# ArduFrauenfelderCNC_0_1-b6.net
KiCad netlist of a schematic drawn in EAGLE
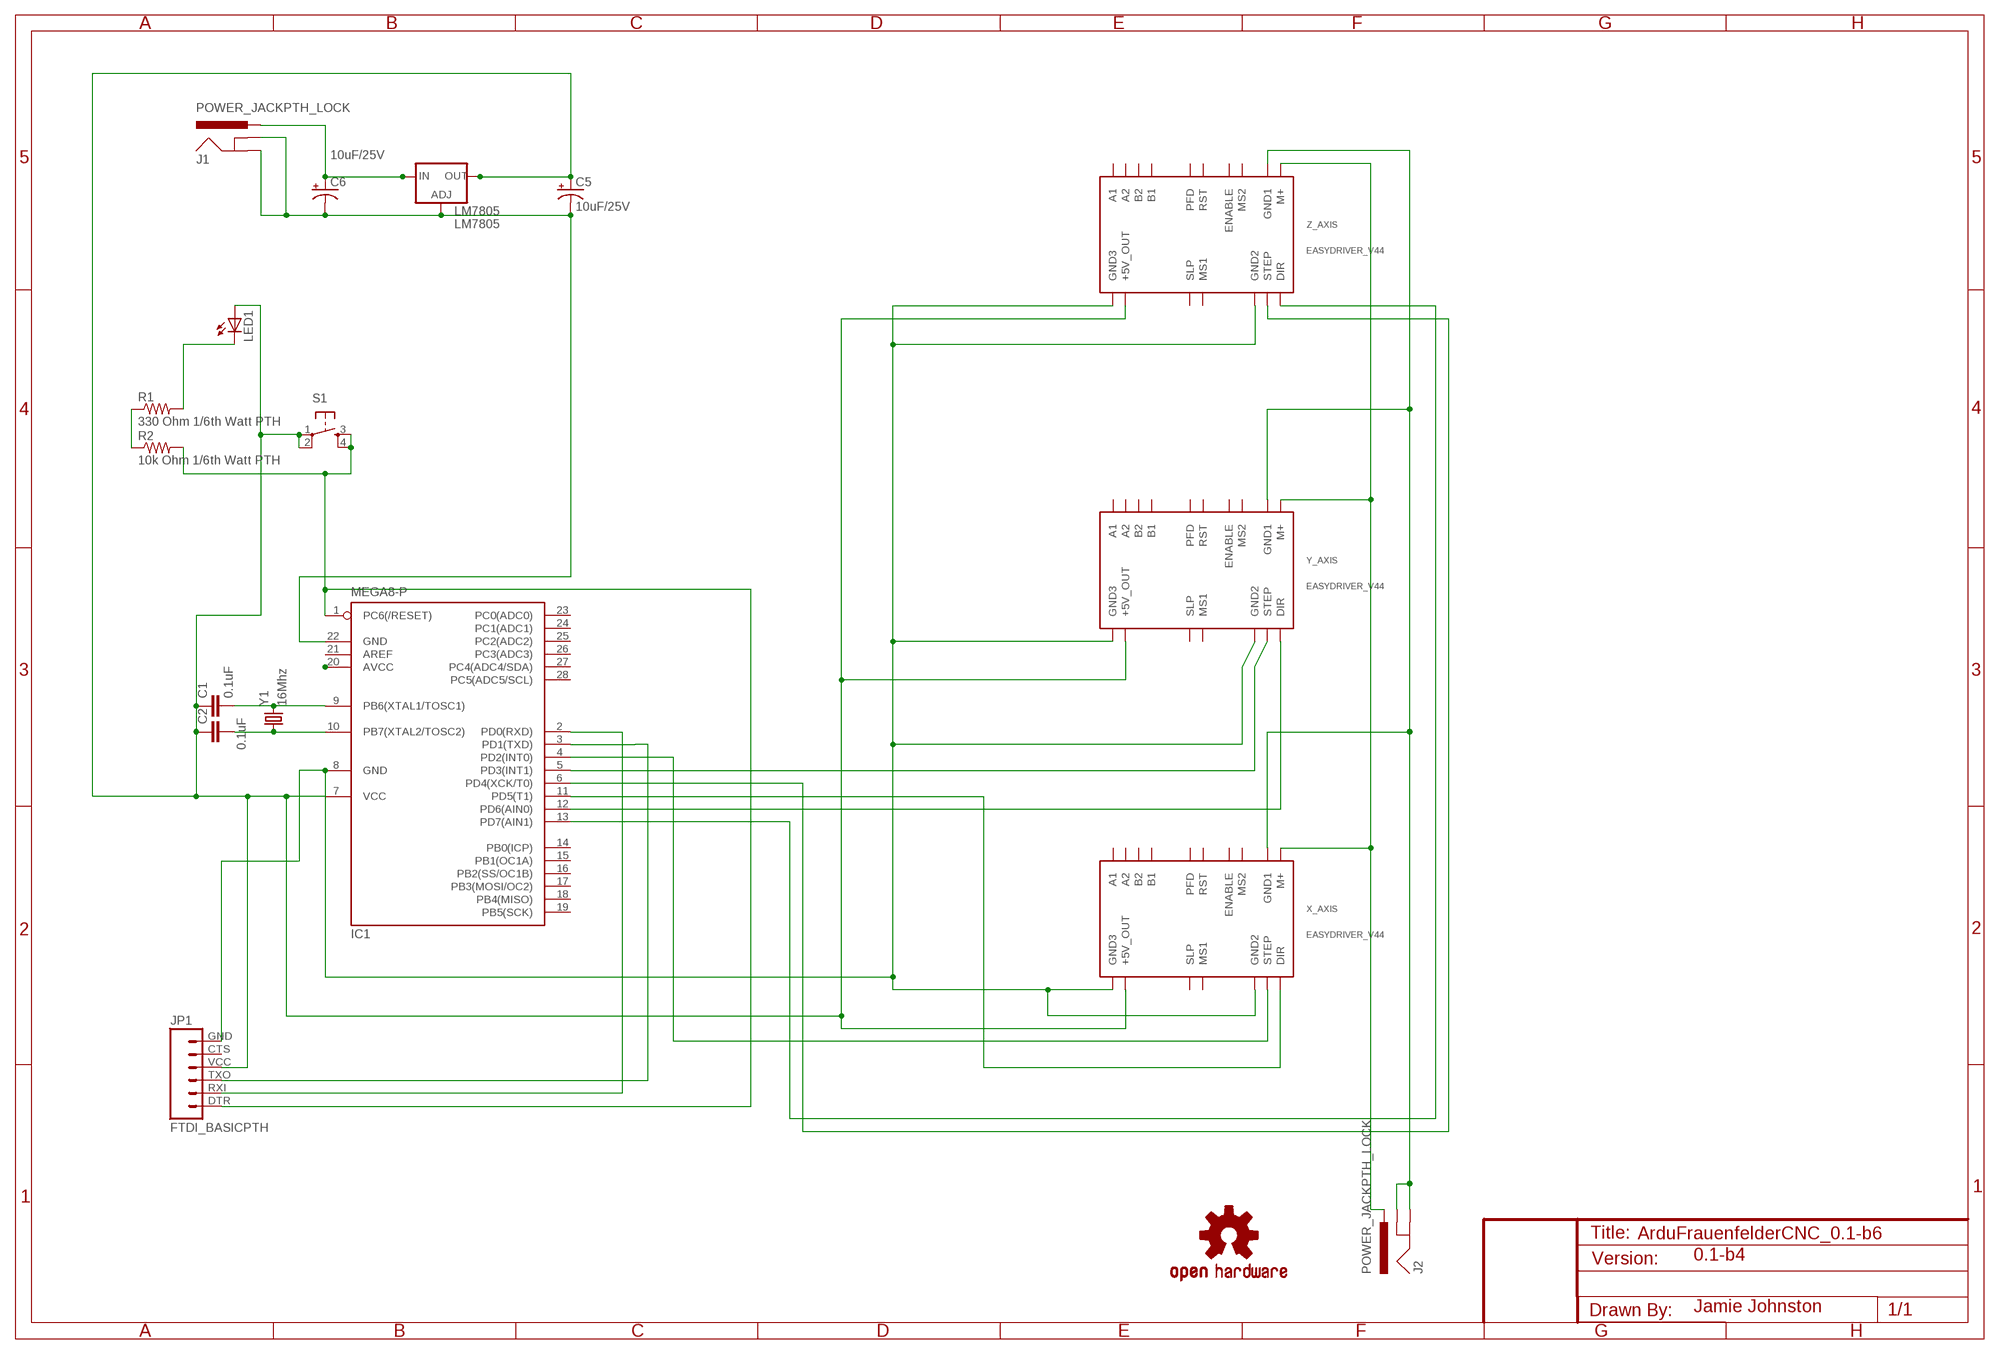
[diagram p0: schematic, sheet 1]

(export (version "E")
  (design (tool "Eeschema 10.0.6"))
  (components
    (comp (ref "C1")
      (value "0.1uF")
      (footprint "eagle-import:CAP-PTH-SMALL")
      (libsource (lib "eagle-import") (part "CAPPTH"))
    )
    (comp (ref "C2")
      (value "0.1uF")
      (footprint "eagle-import:CAP-PTH-SMALL")
      (libsource (lib "eagle-import") (part "CAPPTH"))
    )
    (comp (ref "C5")
      (value "10uF/25V")
      (footprint "eagle-import:CPOL-RADIAL-10UF-25V")
      (libsource (lib "eagle-import") (part "CAP_POLPTH2"))
    )
    (comp (ref "C6")
      (value "10uF/25V")
      (footprint "eagle-import:CPOL-RADIAL-10UF-25V")
      (libsource (lib "eagle-import") (part "CAP_POLPTH2"))
    )
    (comp (ref "IC1")
      (value "MEGA8-P")
      (footprint "eagle-import:DIL28-3")
      (libsource (lib "eagle-import") (part "MEGA8-P"))
    )
    (comp (ref "J1")
      (value "POWER_JACKPTH_LOCK")
      (footprint "eagle-import:POWER_JACK_PTH_LOCK")
      (libsource (lib "eagle-import") (part "POWER_JACKPTH_LOCK"))
    )
    (comp (ref "J2")
      (value "POWER_JACKPTH_LOCK")
      (footprint "eagle-import:POWER_JACK_PTH_LOCK")
      (libsource (lib "eagle-import") (part "POWER_JACKPTH_LOCK"))
    )
    (comp (ref "JP1")
      (value "FTDI_BASICPTH")
      (footprint "eagle-import:FTDI_BASIC")
      (libsource (lib "eagle-import") (part "FTDI_BASICPTH"))
    )
    (comp (ref "LED1")
      (value "LED5MM")
      (footprint "eagle-import:LED5MM")
      (libsource (lib "eagle-import") (part "LED5MM"))
    )
    (comp (ref "LM7805")
      (value "LM7805")
      (footprint "eagle-import:TO220-ADJ")
      (libsource (lib "eagle-import") (part "V_REG_317SINK"))
    )
    (comp (ref "R1")
      (value "330 Ohm 1/6th Watt PTH")
      (footprint "eagle-import:AXIAL-0.4")
      (libsource (lib "eagle-import") (part "RESISTORPTH-1/4W"))
    )
    (comp (ref "R2")
      (value "10k Ohm 1/6th Watt PTH")
      (footprint "eagle-import:AXIAL-0.4")
      (libsource (lib "eagle-import") (part "RESISTORPTH-1/4W"))
    )
    (comp (ref "S1")
      (value "TAC_SWITCHPTH")
      (footprint "eagle-import:TACTILE-PTH")
      (libsource (lib "eagle-import") (part "TAC_SWITCHPTH"))
    )
    (comp (ref "U$2")
      (value "OSHW-LOGOL")
      (footprint "eagle-import:OSHW-LOGO-L")
      (libsource (lib "eagle-import") (part "OSHW-LOGOL"))
    )
    (comp (ref "X_AXIS")
      (value "EASYDRIVER_V44")
      (footprint "eagle-import:EASYDRIVER_V44")
      (libsource (lib "eagle-import") (part "EASYDRIVER_V44"))
    )
    (comp (ref "Y1")
      (value "16Mhz")
      (footprint "eagle-import:HC49US")
      (libsource (lib "eagle-import") (part "CRYSTALHC49US"))
    )
    (comp (ref "Y_AXIS")
      (value "EASYDRIVER_V44")
      (footprint "eagle-import:EASYDRIVER_V44")
      (libsource (lib "eagle-import") (part "EASYDRIVER_V44"))
    )
    (comp (ref "Z_AXIS")
      (value "EASYDRIVER_V44")
      (footprint "eagle-import:EASYDRIVER_V44")
      (libsource (lib "eagle-import") (part "EASYDRIVER_V44"))
    )
  )
  (nets
    (net (code "1") (name "/AVCC") (class "Default")
      (node (ref "IC1") (pin "20") (pinfunction "AVCC_20") (pintype "power_in"))
    )
    (net (code "2") (name "Net-(C5-+)") (class "Default")
      (node (ref "C1") (pin "1") (pinfunction "1_1") (pintype "passive"))
      (node (ref "C2") (pin "1") (pinfunction "1_1") (pintype "passive"))
      (node (ref "C5") (pin "1") (pinfunction "+_1") (pintype "passive"))
      (node (ref "IC1") (pin "7") (pinfunction "VCC_7") (pintype "power_in"))
      (node (ref "JP1") (pin "VCC") (pinfunction "4_VCC") (pintype "passive"))
      (node (ref "LED1") (pin "A") (pinfunction "A_A") (pintype "passive"))
      (node (ref "LM7805") (pin "OUT") (pinfunction "OUT_OUT") (pintype "output"))
      (node (ref "S1") (pin "1") (pinfunction "1_1") (pintype "passive"))
      (node (ref "S1") (pin "2") (pinfunction "2_2") (pintype "passive"))
      (node (ref "X_AXIS") (pin "P$11") (pinfunction "+5V_OUT_P$11") (pintype "bidirectional"))
      (node (ref "Y_AXIS") (pin "P$11") (pinfunction "+5V_OUT_P$11") (pintype "bidirectional"))
      (node (ref "Z_AXIS") (pin "P$11") (pinfunction "+5V_OUT_P$11") (pintype "bidirectional"))
    )
    (net (code "3") (name "Net-(C5--)") (class "Default")
      (node (ref "C5") (pin "2") (pinfunction "-_2") (pintype "passive"))
      (node (ref "C6") (pin "2") (pinfunction "-_2") (pintype "passive"))
      (node (ref "IC1") (pin "22") (pinfunction "GND_22") (pintype "power_in"))
      (node (ref "J1") (pin "GND") (pinfunction "GND_GND") (pintype "bidirectional"))
      (node (ref "J1") (pin "GNDBREAK") (pinfunction "GNDBREAK_GNDBREAK") (pintype "bidirectional"))
      (node (ref "LM7805") (pin "ADJ") (pinfunction "ADJ_ADJ") (pintype "input"))
    )
    (net (code "4") (name "Net-(C6-+)") (class "Default")
      (node (ref "C6") (pin "1") (pinfunction "+_1") (pintype "passive"))
      (node (ref "J1") (pin "PWR") (pinfunction "PWR_PWR") (pintype "bidirectional"))
      (node (ref "LM7805") (pin "IN") (pinfunction "IN_IN") (pintype "input"))
    )
    (net (code "5") (name "Net-(IC1-PB6(XTAL1{slash}TOSC1))") (class "Default")
      (node (ref "C1") (pin "2") (pinfunction "2_2") (pintype "passive"))
      (node (ref "IC1") (pin "9") (pinfunction "PB6(XTAL1/TOSC1)_9") (pintype "bidirectional"))
      (node (ref "Y1") (pin "2") (pinfunction "2_2") (pintype "passive"))
    )
    (net (code "6") (name "Net-(IC1-PB7(XTAL2{slash}TOSC2))") (class "Default")
      (node (ref "C2") (pin "2") (pinfunction "2_2") (pintype "passive"))
      (node (ref "IC1") (pin "10") (pinfunction "PB7(XTAL2/TOSC2)_10") (pintype "bidirectional"))
      (node (ref "Y1") (pin "1") (pinfunction "1_1") (pintype "passive"))
    )
    (net (code "7") (name "Net-(IC1-PC6({slash}RESET))") (class "Default")
      (node (ref "IC1") (pin "1") (pinfunction "PC6(/RESET)_1") (pintype "bidirectional"))
      (node (ref "JP1") (pin "DTR") (pinfunction "1_DTR") (pintype "passive"))
      (node (ref "R2") (pin "P$2") (pinfunction "2_P$2") (pintype "passive"))
      (node (ref "S1") (pin "3") (pinfunction "3_3") (pintype "passive"))
      (node (ref "S1") (pin "4") (pinfunction "4_4") (pintype "passive"))
    )
    (net (code "8") (name "Net-(IC1-PD0(RXD))") (class "Default")
      (node (ref "IC1") (pin "2") (pinfunction "PD0(RXD)_2") (pintype "bidirectional"))
      (node (ref "JP1") (pin "RXI") (pinfunction "2_RXI") (pintype "passive"))
    )
    (net (code "9") (name "Net-(IC1-PD1(TXD))") (class "Default")
      (node (ref "IC1") (pin "3") (pinfunction "PD1(TXD)_3") (pintype "bidirectional"))
      (node (ref "JP1") (pin "TXO") (pinfunction "3_TXO") (pintype "passive"))
    )
    (net (code "10") (name "Net-(IC1-PD2(INT0))") (class "Default")
      (node (ref "IC1") (pin "4") (pinfunction "PD2(INT0)_4") (pintype "bidirectional"))
      (node (ref "X_AXIS") (pin "STEP") (pinfunction "STEP_STEP") (pintype "bidirectional"))
    )
    (net (code "11") (name "Net-(IC1-PD3(INT1))") (class "Default")
      (node (ref "IC1") (pin "5") (pinfunction "PD3(INT1)_5") (pintype "bidirectional"))
      (node (ref "Y_AXIS") (pin "STEP") (pinfunction "STEP_STEP") (pintype "bidirectional"))
    )
    (net (code "12") (name "Net-(IC1-PD4(XCK{slash}T0))") (class "Default")
      (node (ref "IC1") (pin "6") (pinfunction "PD4(XCK/T0)_6") (pintype "bidirectional"))
      (node (ref "Z_AXIS") (pin "STEP") (pinfunction "STEP_STEP") (pintype "bidirectional"))
    )
    (net (code "13") (name "Net-(IC1-PD5(T1))") (class "Default")
      (node (ref "IC1") (pin "11") (pinfunction "PD5(T1)_11") (pintype "bidirectional"))
      (node (ref "X_AXIS") (pin "DIR") (pinfunction "DIR_DIR") (pintype "bidirectional"))
    )
    (net (code "14") (name "Net-(IC1-PD6(AIN0))") (class "Default")
      (node (ref "IC1") (pin "12") (pinfunction "PD6(AIN0)_12") (pintype "bidirectional"))
      (node (ref "Y_AXIS") (pin "DIR") (pinfunction "DIR_DIR") (pintype "bidirectional"))
    )
    (net (code "15") (name "Net-(IC1-PD7(AIN1))") (class "Default")
      (node (ref "IC1") (pin "13") (pinfunction "PD7(AIN1)_13") (pintype "bidirectional"))
      (node (ref "Z_AXIS") (pin "DIR") (pinfunction "DIR_DIR") (pintype "bidirectional"))
    )
    (net (code "16") (name "Net-(J2-PadGND)") (class "Default")
      (node (ref "J2") (pin "GND") (pinfunction "GND_GND") (pintype "bidirectional"))
      (node (ref "J2") (pin "GNDBREAK") (pinfunction "GNDBREAK_GNDBREAK") (pintype "bidirectional"))
      (node (ref "X_AXIS") (pin "GND1") (pinfunction "GND1_GND1") (pintype "bidirectional"))
      (node (ref "Y_AXIS") (pin "GND1") (pinfunction "GND1_GND1") (pintype "bidirectional"))
      (node (ref "Z_AXIS") (pin "GND1") (pinfunction "GND1_GND1") (pintype "bidirectional"))
    )
    (net (code "17") (name "Net-(J2-PadPWR)") (class "Default")
      (node (ref "J2") (pin "PWR") (pinfunction "PWR_PWR") (pintype "bidirectional"))
      (node (ref "X_AXIS") (pin "M+") (pinfunction "M+_M+") (pintype "bidirectional"))
      (node (ref "Y_AXIS") (pin "M+") (pinfunction "M+_M+") (pintype "bidirectional"))
      (node (ref "Z_AXIS") (pin "M+") (pinfunction "M+_M+") (pintype "bidirectional"))
    )
    (net (code "18") (name "Net-(JP1-6)") (class "Default")
      (node (ref "IC1") (pin "8") (pinfunction "GND_8") (pintype "power_in"))
      (node (ref "JP1") (pin "GND") (pinfunction "6_GND") (pintype "passive"))
      (node (ref "X_AXIS") (pin "GND2") (pinfunction "GND2_GND2") (pintype "bidirectional"))
      (node (ref "X_AXIS") (pin "GND3") (pinfunction "GND3_GND3") (pintype "bidirectional"))
      (node (ref "Y_AXIS") (pin "GND2") (pinfunction "GND2_GND2") (pintype "bidirectional"))
      (node (ref "Y_AXIS") (pin "GND3") (pinfunction "GND3_GND3") (pintype "bidirectional"))
      (node (ref "Z_AXIS") (pin "GND2") (pinfunction "GND2_GND2") (pintype "bidirectional"))
      (node (ref "Z_AXIS") (pin "GND3") (pinfunction "GND3_GND3") (pintype "bidirectional"))
    )
    (net (code "19") (name "Net-(LED1-C)") (class "Default")
      (node (ref "LED1") (pin "K") (pinfunction "C_K") (pintype "passive"))
      (node (ref "R1") (pin "P$2") (pinfunction "2_P$2") (pintype "passive"))
    )
    (net (code "20") (name "Net-(R1-1)") (class "Default")
      (node (ref "R1") (pin "P$1") (pinfunction "1_P$1") (pintype "passive"))
      (node (ref "R2") (pin "P$1") (pinfunction "1_P$1") (pintype "passive"))
    )
    (net (code "21") (name "unconnected-(IC1-AREF-Pad21)") (class "Default")
      (node (ref "IC1") (pin "21") (pinfunction "AREF_21") (pintype "passive"))
    )
    (net (code "22") (name "unconnected-(IC1-PB0(ICP)-Pad14)") (class "Default")
      (node (ref "IC1") (pin "14") (pinfunction "PB0(ICP)_14") (pintype "bidirectional"))
    )
    (net (code "23") (name "unconnected-(IC1-PB1(OC1A)-Pad15)") (class "Default")
      (node (ref "IC1") (pin "15") (pinfunction "PB1(OC1A)_15") (pintype "bidirectional"))
    )
    (net (code "24") (name "unconnected-(IC1-PB2(SS{slash}OC1B)-Pad16)") (class "Default")
      (node (ref "IC1") (pin "16") (pinfunction "PB2(SS/OC1B)_16") (pintype "bidirectional"))
    )
    (net (code "25") (name "unconnected-(IC1-PB3(MOSI{slash}OC2)-Pad17)") (class "Default")
      (node (ref "IC1") (pin "17") (pinfunction "PB3(MOSI/OC2)_17") (pintype "bidirectional"))
    )
    (net (code "26") (name "unconnected-(IC1-PB4(MISO)-Pad18)") (class "Default")
      (node (ref "IC1") (pin "18") (pinfunction "PB4(MISO)_18") (pintype "bidirectional"))
    )
    (net (code "27") (name "unconnected-(IC1-PB5(SCK)-Pad19)") (class "Default")
      (node (ref "IC1") (pin "19") (pinfunction "PB5(SCK)_19") (pintype "bidirectional"))
    )
    (net (code "28") (name "unconnected-(IC1-PC0(ADC0)-Pad23)") (class "Default")
      (node (ref "IC1") (pin "23") (pinfunction "PC0(ADC0)_23") (pintype "bidirectional"))
    )
    (net (code "29") (name "unconnected-(IC1-PC1(ADC1)-Pad24)") (class "Default")
      (node (ref "IC1") (pin "24") (pinfunction "PC1(ADC1)_24") (pintype "bidirectional"))
    )
    (net (code "30") (name "unconnected-(IC1-PC2(ADC2)-Pad25)") (class "Default")
      (node (ref "IC1") (pin "25") (pinfunction "PC2(ADC2)_25") (pintype "bidirectional"))
    )
    (net (code "31") (name "unconnected-(IC1-PC3(ADC3)-Pad26)") (class "Default")
      (node (ref "IC1") (pin "26") (pinfunction "PC3(ADC3)_26") (pintype "bidirectional"))
    )
    (net (code "32") (name "unconnected-(IC1-PC4(ADC4{slash}SDA)-Pad27)") (class "Default")
      (node (ref "IC1") (pin "27") (pinfunction "PC4(ADC4/SDA)_27") (pintype "bidirectional"))
    )
    (net (code "33") (name "unconnected-(IC1-PC5(ADC5{slash}SCL)-Pad28)") (class "Default")
      (node (ref "IC1") (pin "28") (pinfunction "PC5(ADC5/SCL)_28") (pintype "bidirectional"))
    )
    (net (code "34") (name "unconnected-(JP1-5-PadCTS)") (class "Default")
      (node (ref "JP1") (pin "CTS") (pinfunction "5_CTS") (pintype "passive"))
    )
    (net (code "35") (name "unconnected-(X_AXIS-PadA1)") (class "Default")
      (node (ref "X_AXIS") (pin "A1") (pinfunction "A1_A1") (pintype "bidirectional"))
    )
    (net (code "36") (name "unconnected-(X_AXIS-PadA2)") (class "Default")
      (node (ref "X_AXIS") (pin "A2") (pinfunction "A2_A2") (pintype "bidirectional"))
    )
    (net (code "37") (name "unconnected-(X_AXIS-PadB1)") (class "Default")
      (node (ref "X_AXIS") (pin "B1") (pinfunction "B1_B1") (pintype "bidirectional"))
    )
    (net (code "38") (name "unconnected-(X_AXIS-PadB2)") (class "Default")
      (node (ref "X_AXIS") (pin "B2") (pinfunction "B2_B2") (pintype "bidirectional"))
    )
    (net (code "39") (name "unconnected-(X_AXIS-PadENABLE)") (class "Default")
      (node (ref "X_AXIS") (pin "ENABLE") (pinfunction "ENABLE_ENABLE") (pintype "bidirectional"))
    )
    (net (code "40") (name "unconnected-(X_AXIS-PadMS1)") (class "Default")
      (node (ref "X_AXIS") (pin "MS1") (pinfunction "MS1_MS1") (pintype "bidirectional"))
    )
    (net (code "41") (name "unconnected-(X_AXIS-PadMS2)") (class "Default")
      (node (ref "X_AXIS") (pin "MS2") (pinfunction "MS2_MS2") (pintype "bidirectional"))
    )
    (net (code "42") (name "unconnected-(X_AXIS-PadPFD)") (class "Default")
      (node (ref "X_AXIS") (pin "PFD") (pinfunction "PFD_PFD") (pintype "bidirectional"))
    )
    (net (code "43") (name "unconnected-(X_AXIS-PadRST)") (class "Default")
      (node (ref "X_AXIS") (pin "RST") (pinfunction "RST_RST") (pintype "bidirectional"))
    )
    (net (code "44") (name "unconnected-(X_AXIS-SLP-PadSLEEP)") (class "Default")
      (node (ref "X_AXIS") (pin "SLEEP") (pinfunction "SLP_SLEEP") (pintype "bidirectional"))
    )
    (net (code "45") (name "unconnected-(Y_AXIS-PadA1)") (class "Default")
      (node (ref "Y_AXIS") (pin "A1") (pinfunction "A1_A1") (pintype "bidirectional"))
    )
    (net (code "46") (name "unconnected-(Y_AXIS-PadA2)") (class "Default")
      (node (ref "Y_AXIS") (pin "A2") (pinfunction "A2_A2") (pintype "bidirectional"))
    )
    (net (code "47") (name "unconnected-(Y_AXIS-PadB1)") (class "Default")
      (node (ref "Y_AXIS") (pin "B1") (pinfunction "B1_B1") (pintype "bidirectional"))
    )
    (net (code "48") (name "unconnected-(Y_AXIS-PadB2)") (class "Default")
      (node (ref "Y_AXIS") (pin "B2") (pinfunction "B2_B2") (pintype "bidirectional"))
    )
    (net (code "49") (name "unconnected-(Y_AXIS-PadENABLE)") (class "Default")
      (node (ref "Y_AXIS") (pin "ENABLE") (pinfunction "ENABLE_ENABLE") (pintype "bidirectional"))
    )
    (net (code "50") (name "unconnected-(Y_AXIS-PadMS1)") (class "Default")
      (node (ref "Y_AXIS") (pin "MS1") (pinfunction "MS1_MS1") (pintype "bidirectional"))
    )
    (net (code "51") (name "unconnected-(Y_AXIS-PadMS2)") (class "Default")
      (node (ref "Y_AXIS") (pin "MS2") (pinfunction "MS2_MS2") (pintype "bidirectional"))
    )
    (net (code "52") (name "unconnected-(Y_AXIS-PadPFD)") (class "Default")
      (node (ref "Y_AXIS") (pin "PFD") (pinfunction "PFD_PFD") (pintype "bidirectional"))
    )
    (net (code "53") (name "unconnected-(Y_AXIS-PadRST)") (class "Default")
      (node (ref "Y_AXIS") (pin "RST") (pinfunction "RST_RST") (pintype "bidirectional"))
    )
    (net (code "54") (name "unconnected-(Y_AXIS-SLP-PadSLEEP)") (class "Default")
      (node (ref "Y_AXIS") (pin "SLEEP") (pinfunction "SLP_SLEEP") (pintype "bidirectional"))
    )
    (net (code "55") (name "unconnected-(Z_AXIS-PadA1)") (class "Default")
      (node (ref "Z_AXIS") (pin "A1") (pinfunction "A1_A1") (pintype "bidirectional"))
    )
    (net (code "56") (name "unconnected-(Z_AXIS-PadA2)") (class "Default")
      (node (ref "Z_AXIS") (pin "A2") (pinfunction "A2_A2") (pintype "bidirectional"))
    )
    (net (code "57") (name "unconnected-(Z_AXIS-PadB1)") (class "Default")
      (node (ref "Z_AXIS") (pin "B1") (pinfunction "B1_B1") (pintype "bidirectional"))
    )
    (net (code "58") (name "unconnected-(Z_AXIS-PadB2)") (class "Default")
      (node (ref "Z_AXIS") (pin "B2") (pinfunction "B2_B2") (pintype "bidirectional"))
    )
    (net (code "59") (name "unconnected-(Z_AXIS-PadENABLE)") (class "Default")
      (node (ref "Z_AXIS") (pin "ENABLE") (pinfunction "ENABLE_ENABLE") (pintype "bidirectional"))
    )
    (net (code "60") (name "unconnected-(Z_AXIS-PadMS1)") (class "Default")
      (node (ref "Z_AXIS") (pin "MS1") (pinfunction "MS1_MS1") (pintype "bidirectional"))
    )
    (net (code "61") (name "unconnected-(Z_AXIS-PadMS2)") (class "Default")
      (node (ref "Z_AXIS") (pin "MS2") (pinfunction "MS2_MS2") (pintype "bidirectional"))
    )
    (net (code "62") (name "unconnected-(Z_AXIS-PadPFD)") (class "Default")
      (node (ref "Z_AXIS") (pin "PFD") (pinfunction "PFD_PFD") (pintype "bidirectional"))
    )
    (net (code "63") (name "unconnected-(Z_AXIS-PadRST)") (class "Default")
      (node (ref "Z_AXIS") (pin "RST") (pinfunction "RST_RST") (pintype "bidirectional"))
    )
    (net (code "64") (name "unconnected-(Z_AXIS-SLP-PadSLEEP)") (class "Default")
      (node (ref "Z_AXIS") (pin "SLEEP") (pinfunction "SLP_SLEEP") (pintype "bidirectional"))
    )
  )
)
